# fr4_light_sensor_programmer.net
KiCad netlist of a schematic drawn in Altium Designer
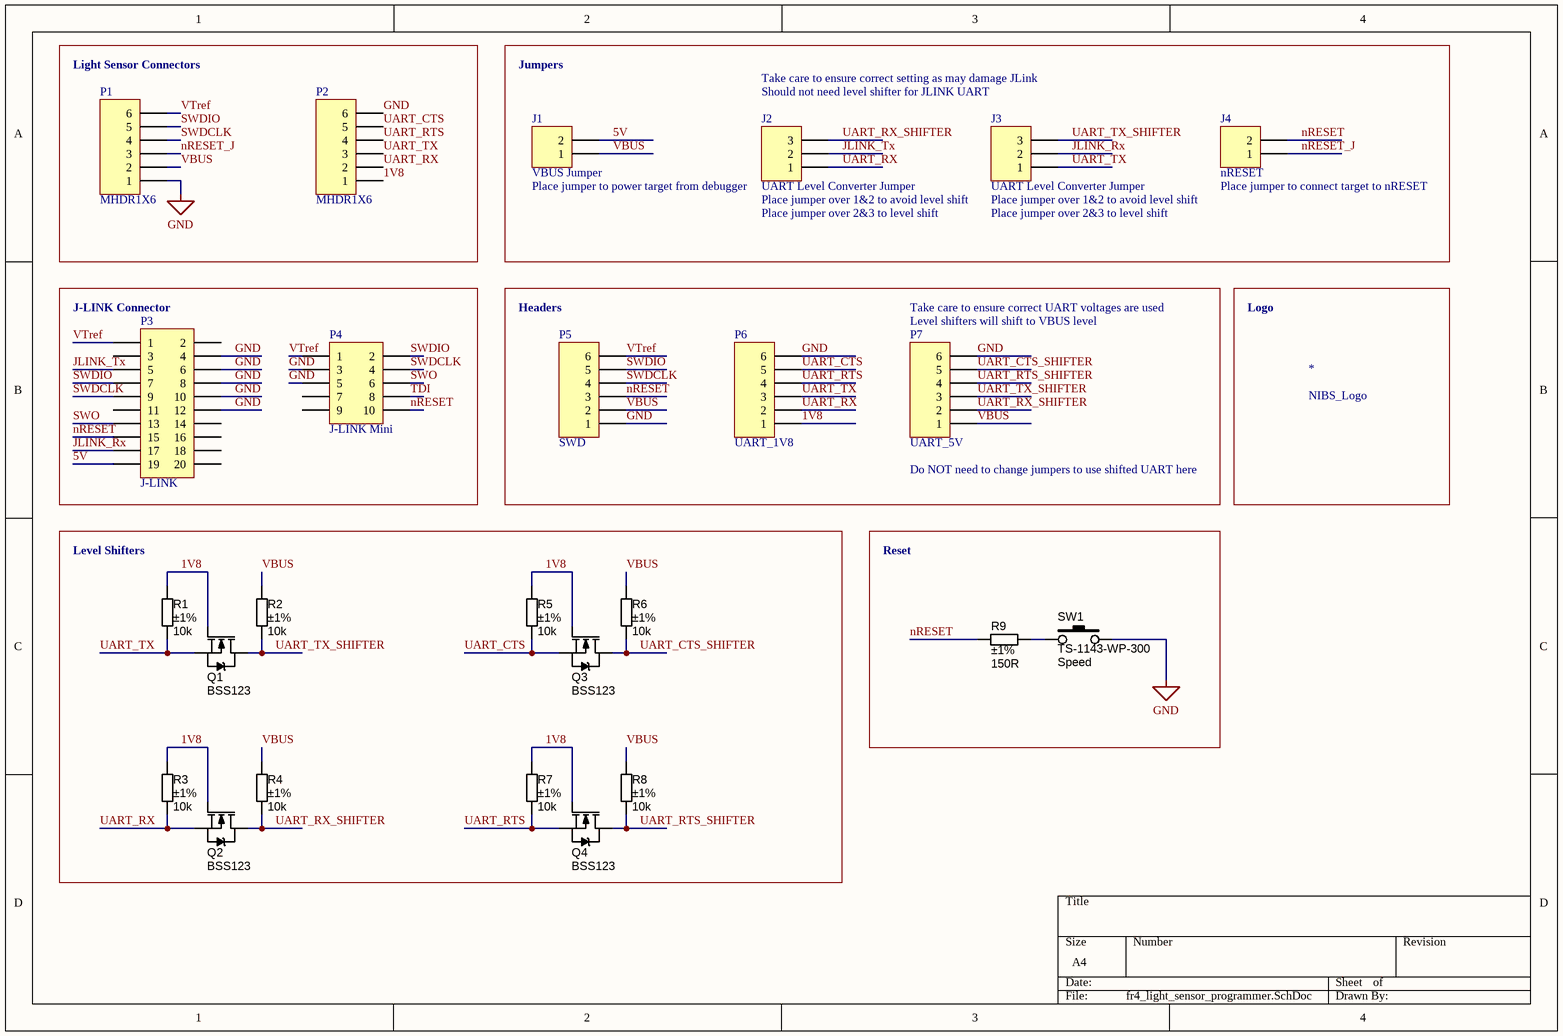
[diagram p0: fr4_light_sensor_programmer.SchDoc]

(export (version "E")
  (design (tool "Eeschema 10.0.6"))
  (components
    (comp (ref "*")
      (value "NIBS_Logo")
      (footprint "Logo")
      (libsource (lib "Light Sensor Prototype") (part "NIBS_Logo"))
    )
    (comp (ref "J1")
      (value "VBUS Jumper")
      (footprint "HDR1X2")
      (description "Header, 2-Pin")
      (fields (field (name "PUBLISHER") "Altium Limited"))
      (libsource (lib "Miscellaneous Connectors") (part "Header 2"))
    )
    (comp (ref "J2")
      (value "UART Level Converter Jumper")
      (footprint "HDR1X3")
      (description "Header, 3-Pin")
      (fields (field (name "PUBLISHER") "Altium Limited"))
      (libsource (lib "Miscellaneous Connectors") (part "Header 3"))
    )
    (comp (ref "J3")
      (value "UART Level Converter Jumper")
      (footprint "HDR1X3")
      (description "Header, 3-Pin")
      (fields (field (name "PUBLISHER") "Altium Limited"))
      (libsource (lib "Miscellaneous Connectors") (part "Header 3"))
    )
    (comp (ref "J4")
      (value "nRESET")
      (footprint "HDR1X2")
      (description "Header, 2-Pin")
      (fields (field (name "PUBLISHER") "Altium Limited"))
      (libsource (lib "Miscellaneous Connectors") (part "Header 2"))
    )
    (comp (ref "P1")
      (value "MHDR1X6")
      (footprint "MHDR1X6")
      (description "Header, 6-Pin")
      (fields (field (name "PUBLISHER") "Altium Limited"))
      (libsource (lib "Miscellaneous Connectors") (part "MHDR1X6"))
    )
    (comp (ref "P2")
      (value "MHDR1X6")
      (footprint "MHDR1X6")
      (description "Header, 6-Pin")
      (fields (field (name "PUBLISHER") "Altium Limited"))
      (libsource (lib "Miscellaneous Connectors") (part "MHDR1X6"))
    )
    (comp (ref "P3")
      (value "J-LINK")
      (footprint "HDR2X10")
      (description "Header, 10-Pin, Dual row")
      (fields (field (name "PUBLISHER") "Altium Limited"))
      (libsource (lib "Miscellaneous Connectors") (part "Header 10X2"))
    )
    (comp (ref "P4")
      (value "J-LINK Mini")
      (footprint "MHDR2X5")
      (description "Header, 5-Pin, Dual row")
      (fields (field (name "PUBLISHER") "Altium Limited"))
      (libsource (lib "Miscellaneous Connectors") (part "MHDR2X5"))
    )
    (comp (ref "P5")
      (value "SWD")
      (footprint "HDR1X6")
      (description "Header, 6-Pin")
      (fields (field (name "PUBLISHER") "Altium Limited"))
      (libsource (lib "Miscellaneous Connectors") (part "Header 6"))
    )
    (comp (ref "P6")
      (value "UART_1V8")
      (footprint "HDR1X6")
      (description "Header, 6-Pin")
      (fields (field (name "PUBLISHER") "Altium Limited"))
      (libsource (lib "Miscellaneous Connectors") (part "Header 6"))
    )
    (comp (ref "P7")
      (value "UART_5V")
      (footprint "HDR1X6")
      (description "Header, 6-Pin")
      (fields (field (name "PUBLISHER") "Altium Limited"))
      (libsource (lib "Miscellaneous Connectors") (part "Header 6"))
    )
    (comp (ref "Q1")
      (value "BSS123")
      (footprint "SOT23-3")
      (description "MOSFET SMD N-CH 100V 170mA SOT23-3")
      (libsource (lib "Libs_RRutledge") (part "MOSFET_BSS123"))
    )
    (comp (ref "Q2")
      (value "BSS123")
      (footprint "SOT23-3")
      (description "MOSFET SMD N-CH 100V 170mA SOT23-3")
      (libsource (lib "Libs_RRutledge") (part "MOSFET_BSS123"))
    )
    (comp (ref "Q3")
      (value "BSS123")
      (footprint "SOT23-3")
      (description "MOSFET SMD N-CH 100V 170mA SOT23-3")
      (libsource (lib "Libs_RRutledge") (part "MOSFET_BSS123"))
    )
    (comp (ref "Q4")
      (value "BSS123")
      (footprint "SOT23-3")
      (description "MOSFET SMD N-CH 100V 170mA SOT23-3")
      (libsource (lib "Libs_RRutledge") (part "MOSFET_BSS123"))
    )
    (comp (ref "R1")
      (value "10k")
      (footprint "RESC1608X55N")
      (description "Resistor SMD chip 10k Ohm 0.1W 1% 0603")
      (fields (field (name "TOLERANCE") "±1%") (field (name "Comment") "Thick Film"))
      (libsource (lib "") (part "RES_10K_0603_1%_1"))
    )
    (comp (ref "R2")
      (value "10k")
      (footprint "RESC1608X55N")
      (description "Resistor SMD chip 10k Ohm 0.1W 1% 0603")
      (fields (field (name "TOLERANCE") "±1%") (field (name "Comment") "Thick Film"))
      (libsource (lib "") (part "RES_10K_0603_1%_1"))
    )
    (comp (ref "R3")
      (value "10k")
      (footprint "RESC1608X55N")
      (description "Resistor SMD chip 10k Ohm 0.1W 1% 0603")
      (fields (field (name "TOLERANCE") "±1%") (field (name "Comment") "Thick Film"))
      (libsource (lib "") (part "RES_10K_0603_1%_1"))
    )
    (comp (ref "R4")
      (value "10k")
      (footprint "RESC1608X55N")
      (description "Resistor SMD chip 10k Ohm 0.1W 1% 0603")
      (fields (field (name "TOLERANCE") "±1%") (field (name "Comment") "Thick Film"))
      (libsource (lib "") (part "RES_10K_0603_1%_1"))
    )
    (comp (ref "R5")
      (value "10k")
      (footprint "RESC1608X55N")
      (description "Resistor SMD chip 10k Ohm 0.1W 1% 0603")
      (fields (field (name "TOLERANCE") "±1%") (field (name "Comment") "Thick Film"))
      (libsource (lib "") (part "RES_10K_0603_1%_1"))
    )
    (comp (ref "R6")
      (value "10k")
      (footprint "RESC1608X55N")
      (description "Resistor SMD chip 10k Ohm 0.1W 1% 0603")
      (fields (field (name "TOLERANCE") "±1%") (field (name "Comment") "Thick Film"))
      (libsource (lib "") (part "RES_10K_0603_1%_1"))
    )
    (comp (ref "R7")
      (value "10k")
      (footprint "RESC1608X55N")
      (description "Resistor SMD chip 10k Ohm 0.1W 1% 0603")
      (fields (field (name "TOLERANCE") "±1%") (field (name "Comment") "Thick Film"))
      (libsource (lib "") (part "RES_10K_0603_1%_1"))
    )
    (comp (ref "R8")
      (value "10k")
      (footprint "RESC1608X55N")
      (description "Resistor SMD chip 10k Ohm 0.1W 1% 0603")
      (fields (field (name "TOLERANCE") "±1%") (field (name "Comment") "Thick Film"))
      (libsource (lib "") (part "RES_10K_0603_1%_1"))
    )
    (comp (ref "R9")
      (value "150R")
      (footprint "RESC1608X55N")
      (description "Resistor SMD chip 10k Ohm 0.1W 1% 0603")
      (fields (field (name "TOLERANCE") "±1%") (field (name "Comment") "Thick Film"))
      (libsource (lib "Libs_RRutledge") (part "RES_10K_0603_1%"))
    )
    (comp (ref "SW1")
      (value "SW_THT_PB_4.3mm")
      (footprint "TACT-SWITCH-TS1143")
      (description "Switch, tact, 4.3mm stem")
      (fields (field (name "MANUFACTURER PART NUMBER 1") "TS-1143-WP-300") (field (name "FUNCTION") "Speed"))
      (libsource (lib "Libs_RRutledge") (part "SW_THT_PB_4.3mm"))
    )
  )
  (nets
    (net (code "1") (name "/1V8") (class "Default")
      (node (ref "P2") (pin "1") (pinfunction "1_1") (pintype "passive"))
      (node (ref "P6") (pin "1") (pinfunction "1_1") (pintype "passive"))
      (node (ref "Q1") (pin "1") (pinfunction "G_1") (pintype "passive"))
      (node (ref "Q2") (pin "1") (pinfunction "G_1") (pintype "passive"))
      (node (ref "Q3") (pin "1") (pinfunction "G_1") (pintype "passive"))
      (node (ref "Q4") (pin "1") (pinfunction "G_1") (pintype "passive"))
      (node (ref "R1") (pin "1") (pinfunction "1_1") (pintype "passive"))
      (node (ref "R3") (pin "1") (pinfunction "1_1") (pintype "passive"))
      (node (ref "R5") (pin "1") (pinfunction "1_1") (pintype "passive"))
      (node (ref "R7") (pin "1") (pinfunction "1_1") (pintype "passive"))
    )
    (net (code "2") (name "/5V") (class "Default")
      (node (ref "J1") (pin "2") (pinfunction "2_2") (pintype "passive"))
      (node (ref "P3") (pin "19") (pinfunction "19_19") (pintype "passive"))
    )
    (net (code "3") (name "/JLINK_Rx") (class "Default")
      (node (ref "J3") (pin "2") (pinfunction "2_2") (pintype "passive"))
      (node (ref "P3") (pin "17") (pinfunction "17_17") (pintype "passive"))
    )
    (net (code "4") (name "/JLINK_Tx") (class "Default")
      (node (ref "J2") (pin "2") (pinfunction "2_2") (pintype "passive"))
      (node (ref "P3") (pin "5") (pinfunction "5_5") (pintype "passive"))
    )
    (net (code "5") (name "/SWDCLK") (class "Default")
      (node (ref "P1") (pin "4") (pinfunction "4_4") (pintype "passive"))
      (node (ref "P3") (pin "9") (pinfunction "9_9") (pintype "passive"))
      (node (ref "P4") (pin "4") (pinfunction "4_4") (pintype "passive"))
      (node (ref "P5") (pin "4") (pinfunction "4_4") (pintype "passive"))
    )
    (net (code "6") (name "/SWDIO") (class "Default")
      (node (ref "P1") (pin "5") (pinfunction "5_5") (pintype "passive"))
      (node (ref "P3") (pin "7") (pinfunction "7_7") (pintype "passive"))
      (node (ref "P4") (pin "2") (pinfunction "2_2") (pintype "passive"))
      (node (ref "P5") (pin "5") (pinfunction "5_5") (pintype "passive"))
    )
    (net (code "7") (name "/SWO") (class "Default")
      (node (ref "P3") (pin "13") (pinfunction "13_13") (pintype "passive"))
      (node (ref "P4") (pin "6") (pinfunction "6_6") (pintype "passive"))
    )
    (net (code "8") (name "/TDI") (class "Default")
      (node (ref "P4") (pin "8") (pinfunction "8_8") (pintype "passive"))
    )
    (net (code "9") (name "/UART_CTS") (class "Default")
      (node (ref "P2") (pin "5") (pinfunction "5_5") (pintype "passive"))
      (node (ref "P6") (pin "5") (pinfunction "5_5") (pintype "passive"))
      (node (ref "Q3") (pin "2") (pinfunction "S_2") (pintype "passive"))
      (node (ref "R5") (pin "2") (pinfunction "2_2") (pintype "passive"))
    )
    (net (code "10") (name "/UART_CTS_SHIFTER") (class "Default")
      (node (ref "P7") (pin "5") (pinfunction "5_5") (pintype "passive"))
      (node (ref "Q3") (pin "3") (pinfunction "D_3") (pintype "passive"))
      (node (ref "R6") (pin "2") (pinfunction "2_2") (pintype "passive"))
    )
    (net (code "11") (name "/UART_RTS") (class "Default")
      (node (ref "P2") (pin "4") (pinfunction "4_4") (pintype "passive"))
      (node (ref "P6") (pin "4") (pinfunction "4_4") (pintype "passive"))
      (node (ref "Q4") (pin "2") (pinfunction "S_2") (pintype "passive"))
      (node (ref "R7") (pin "2") (pinfunction "2_2") (pintype "passive"))
    )
    (net (code "12") (name "/UART_RTS_SHIFTER") (class "Default")
      (node (ref "P7") (pin "4") (pinfunction "4_4") (pintype "passive"))
      (node (ref "Q4") (pin "3") (pinfunction "D_3") (pintype "passive"))
      (node (ref "R8") (pin "2") (pinfunction "2_2") (pintype "passive"))
    )
    (net (code "13") (name "/UART_RX") (class "Default")
      (node (ref "J2") (pin "1") (pinfunction "1_1") (pintype "passive"))
      (node (ref "P2") (pin "2") (pinfunction "2_2") (pintype "passive"))
      (node (ref "P6") (pin "2") (pinfunction "2_2") (pintype "passive"))
      (node (ref "Q2") (pin "2") (pinfunction "S_2") (pintype "passive"))
      (node (ref "R3") (pin "2") (pinfunction "2_2") (pintype "passive"))
    )
    (net (code "14") (name "/UART_RX_SHIFTER") (class "Default")
      (node (ref "J2") (pin "3") (pinfunction "3_3") (pintype "passive"))
      (node (ref "P7") (pin "2") (pinfunction "2_2") (pintype "passive"))
      (node (ref "Q2") (pin "3") (pinfunction "D_3") (pintype "passive"))
      (node (ref "R4") (pin "2") (pinfunction "2_2") (pintype "passive"))
    )
    (net (code "15") (name "/UART_TX") (class "Default")
      (node (ref "J3") (pin "1") (pinfunction "1_1") (pintype "passive"))
      (node (ref "P2") (pin "3") (pinfunction "3_3") (pintype "passive"))
      (node (ref "P6") (pin "3") (pinfunction "3_3") (pintype "passive"))
      (node (ref "Q1") (pin "2") (pinfunction "S_2") (pintype "passive"))
      (node (ref "R1") (pin "2") (pinfunction "2_2") (pintype "passive"))
    )
    (net (code "16") (name "/UART_TX_SHIFTER") (class "Default")
      (node (ref "J3") (pin "3") (pinfunction "3_3") (pintype "passive"))
      (node (ref "P7") (pin "3") (pinfunction "3_3") (pintype "passive"))
      (node (ref "Q1") (pin "3") (pinfunction "D_3") (pintype "passive"))
      (node (ref "R2") (pin "2") (pinfunction "2_2") (pintype "passive"))
    )
    (net (code "17") (name "/VBUS") (class "Default")
      (node (ref "J1") (pin "1") (pinfunction "1_1") (pintype "passive"))
      (node (ref "P1") (pin "2") (pinfunction "2_2") (pintype "passive"))
      (node (ref "P5") (pin "2") (pinfunction "2_2") (pintype "passive"))
      (node (ref "P7") (pin "1") (pinfunction "1_1") (pintype "passive"))
      (node (ref "R2") (pin "1") (pinfunction "1_1") (pintype "passive"))
      (node (ref "R4") (pin "1") (pinfunction "1_1") (pintype "passive"))
      (node (ref "R6") (pin "1") (pinfunction "1_1") (pintype "passive"))
      (node (ref "R8") (pin "1") (pinfunction "1_1") (pintype "passive"))
    )
    (net (code "18") (name "/VTref") (class "Default")
      (node (ref "P1") (pin "6") (pinfunction "6_6") (pintype "passive"))
      (node (ref "P3") (pin "1") (pinfunction "1_1") (pintype "passive"))
      (node (ref "P4") (pin "1") (pinfunction "1_1") (pintype "passive"))
      (node (ref "P5") (pin "6") (pinfunction "6_6") (pintype "passive"))
    )
    (net (code "19") (name "/nRESET") (class "Default")
      (node (ref "J4") (pin "2") (pinfunction "2_2") (pintype "passive"))
      (node (ref "P3") (pin "15") (pinfunction "15_15") (pintype "passive"))
      (node (ref "P4") (pin "10") (pinfunction "10_10") (pintype "passive"))
      (node (ref "P5") (pin "3") (pinfunction "3_3") (pintype "passive"))
      (node (ref "R9") (pin "1") (pinfunction "1_1") (pintype "passive"))
    )
    (net (code "20") (name "/nRESET_J") (class "Default")
      (node (ref "J4") (pin "1") (pinfunction "1_1") (pintype "passive"))
      (node (ref "P1") (pin "3") (pinfunction "3_3") (pintype "passive"))
    )
    (net (code "21") (name "GND") (class "Default")
      (node (ref "P1") (pin "1") (pinfunction "1_1") (pintype "passive"))
      (node (ref "P2") (pin "6") (pinfunction "6_6") (pintype "passive"))
      (node (ref "P3") (pin "10") (pinfunction "10_10") (pintype "passive"))
      (node (ref "P3") (pin "12") (pinfunction "12_12") (pintype "passive"))
      (node (ref "P3") (pin "4") (pinfunction "4_4") (pintype "passive"))
      (node (ref "P3") (pin "6") (pinfunction "6_6") (pintype "passive"))
      (node (ref "P3") (pin "8") (pinfunction "8_8") (pintype "passive"))
      (node (ref "P4") (pin "3") (pinfunction "3_3") (pintype "passive"))
      (node (ref "P4") (pin "5") (pinfunction "5_5") (pintype "passive"))
      (node (ref "P5") (pin "1") (pinfunction "1_1") (pintype "passive"))
      (node (ref "P6") (pin "6") (pinfunction "6_6") (pintype "passive"))
      (node (ref "P7") (pin "6") (pinfunction "6_6") (pintype "passive"))
      (node (ref "SW1") (pin "2") (pintype "passive"))
    )
    (net (code "22") (name "Net-(R9-Pad2)") (class "Default")
      (node (ref "R9") (pin "2") (pinfunction "2_2") (pintype "passive"))
      (node (ref "SW1") (pin "1") (pintype "passive"))
    )
    (net (code "23") (name "unconnected-(P3-Pad2)") (class "Default")
      (node (ref "P3") (pin "2") (pinfunction "2_2") (pintype "passive"))
    )
    (net (code "24") (name "unconnected-(P3-Pad3)") (class "Default")
      (node (ref "P3") (pin "3") (pinfunction "3_3") (pintype "passive"))
    )
    (net (code "25") (name "unconnected-(P3-Pad11)") (class "Default")
      (node (ref "P3") (pin "11") (pinfunction "11_11") (pintype "passive"))
    )
    (net (code "26") (name "unconnected-(P3-Pad14)") (class "Default")
      (node (ref "P3") (pin "14") (pinfunction "14_14") (pintype "passive"))
    )
    (net (code "27") (name "unconnected-(P3-Pad16)") (class "Default")
      (node (ref "P3") (pin "16") (pinfunction "16_16") (pintype "passive"))
    )
    (net (code "28") (name "unconnected-(P3-Pad18)") (class "Default")
      (node (ref "P3") (pin "18") (pinfunction "18_18") (pintype "passive"))
    )
    (net (code "29") (name "unconnected-(P3-Pad20)") (class "Default")
      (node (ref "P3") (pin "20") (pinfunction "20_20") (pintype "passive"))
    )
    (net (code "30") (name "unconnected-(P4-Pad7)") (class "Default")
      (node (ref "P4") (pin "7") (pinfunction "7_7") (pintype "passive"))
    )
    (net (code "31") (name "unconnected-(P4-Pad9)") (class "Default")
      (node (ref "P4") (pin "9") (pinfunction "9_9") (pintype "passive"))
    )
  )
)
